# CUBE_SCHEMATIC.net
KiCad netlist of a schematic drawn in Altium Designer
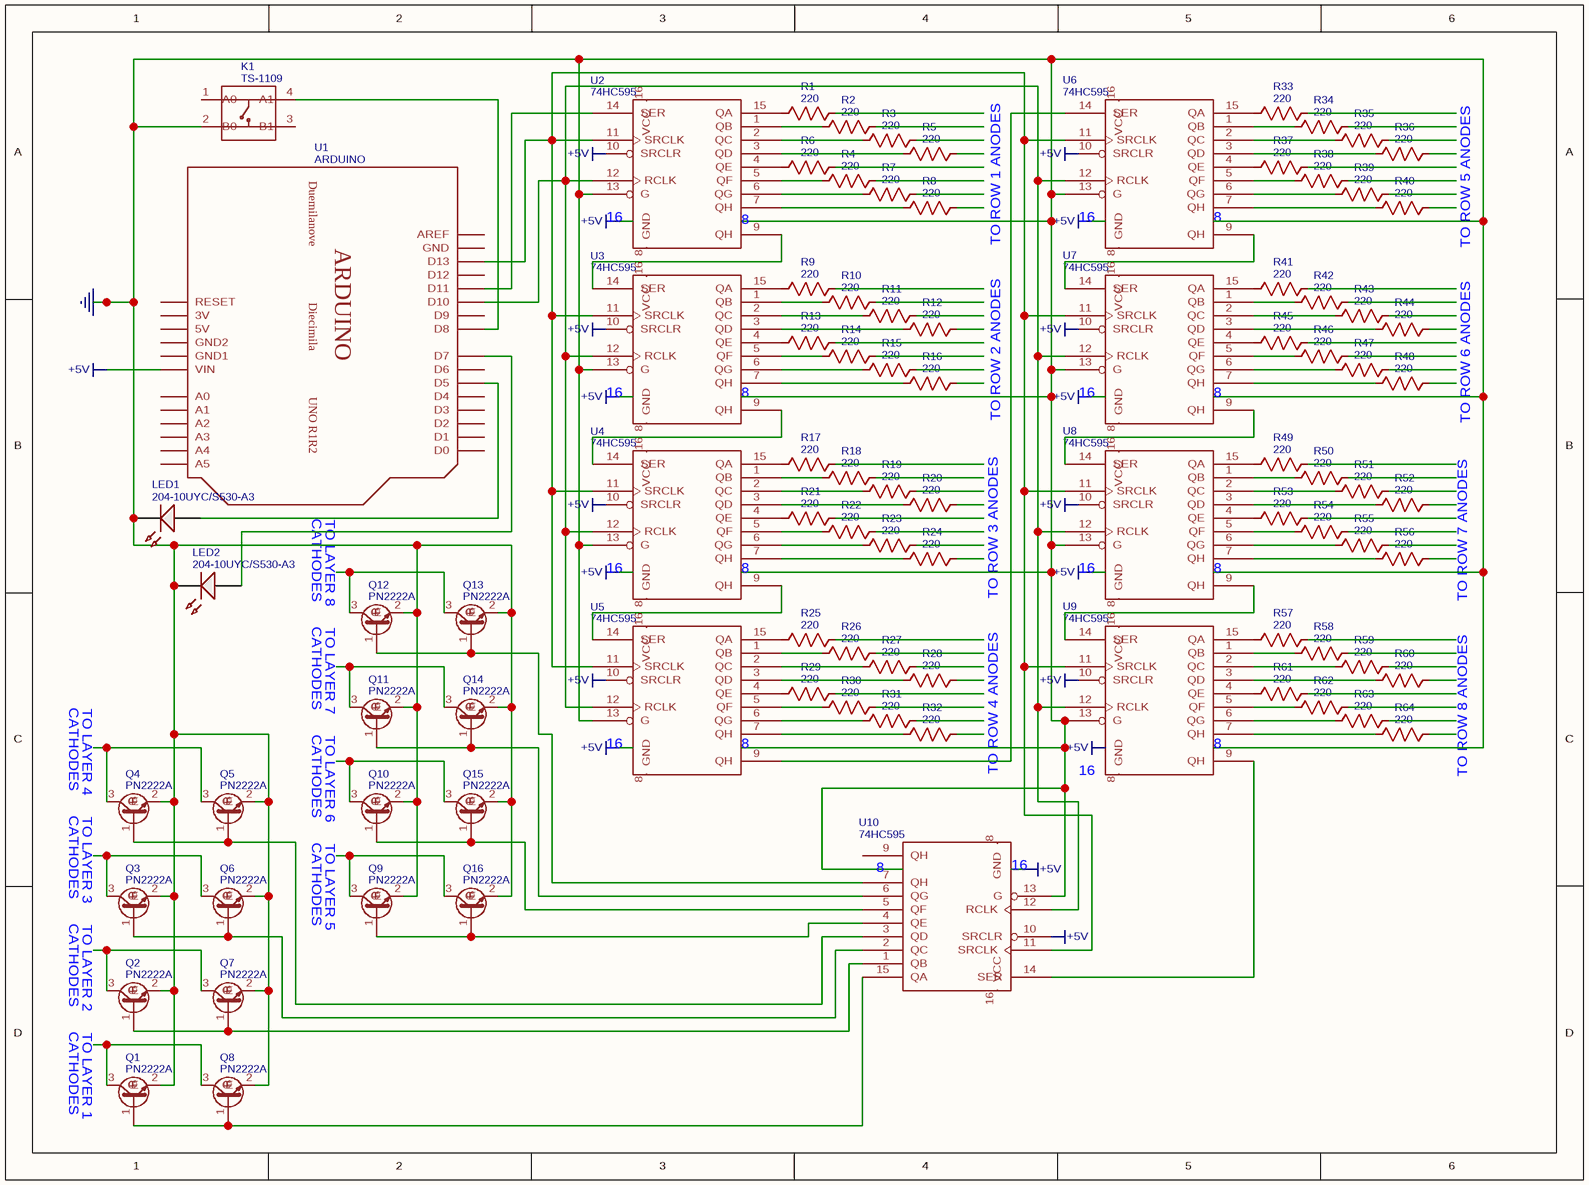
[diagram p0: CUBE+SCHEMATIC.schdoc]

(export (version "E")
  (design (tool "Eeschema 10.0.6"))
  (components
    (comp (ref "K1")
      (value "TS-1109")
      (description "SWITCH TACTILE SPST-NO 0.05A 12V")
      (libsource (lib "") (part "root_0___1"))
    )
    (comp (ref "LED1") (value "204-10UYC/S530-A3") (libsource (lib "") (part "root_2___1")))
    (comp (ref "LED2") (value "204-10UYC/S530-A3") (libsource (lib "") (part "root_2___1")))
    (comp (ref "Q1")
      (value "PN2222A")
      (fields (field (name "BOM_MANUFACTURER PART") "?") (field (name "CONTRIBUTOR") "KiCad"))
      (libsource (lib "altium-import") (part "root_1__"))
    )
    (comp (ref "Q2")
      (value "PN2222A")
      (fields (field (name "BOM_MANUFACTURER PART") "?") (field (name "CONTRIBUTOR") "KiCad"))
      (libsource (lib "altium-import") (part "root_1__"))
    )
    (comp (ref "Q3")
      (value "PN2222A")
      (fields (field (name "BOM_MANUFACTURER PART") "?") (field (name "CONTRIBUTOR") "KiCad"))
      (libsource (lib "altium-import") (part "root_1__"))
    )
    (comp (ref "Q4")
      (value "PN2222A")
      (fields (field (name "BOM_MANUFACTURER PART") "?") (field (name "CONTRIBUTOR") "KiCad"))
      (libsource (lib "altium-import") (part "root_1__"))
    )
    (comp (ref "Q5")
      (value "PN2222A")
      (fields (field (name "BOM_MANUFACTURER PART") "?") (field (name "CONTRIBUTOR") "KiCad"))
      (libsource (lib "altium-import") (part "root_1__"))
    )
    (comp (ref "Q6")
      (value "PN2222A")
      (fields (field (name "BOM_MANUFACTURER PART") "?") (field (name "CONTRIBUTOR") "KiCad"))
      (libsource (lib "altium-import") (part "root_1__"))
    )
    (comp (ref "Q7")
      (value "PN2222A")
      (fields (field (name "BOM_MANUFACTURER PART") "?") (field (name "CONTRIBUTOR") "KiCad"))
      (libsource (lib "altium-import") (part "root_1__"))
    )
    (comp (ref "Q8")
      (value "PN2222A")
      (fields (field (name "BOM_MANUFACTURER PART") "?") (field (name "CONTRIBUTOR") "KiCad"))
      (libsource (lib "altium-import") (part "root_1__"))
    )
    (comp (ref "Q9")
      (value "PN2222A")
      (fields (field (name "BOM_MANUFACTURER PART") "?") (field (name "CONTRIBUTOR") "KiCad"))
      (libsource (lib "altium-import") (part "root_1__"))
    )
    (comp (ref "Q10")
      (value "PN2222A")
      (fields (field (name "BOM_MANUFACTURER PART") "?") (field (name "CONTRIBUTOR") "KiCad"))
      (libsource (lib "altium-import") (part "root_1__"))
    )
    (comp (ref "Q11")
      (value "PN2222A")
      (fields (field (name "BOM_MANUFACTURER PART") "?") (field (name "CONTRIBUTOR") "KiCad"))
      (libsource (lib "altium-import") (part "root_1__"))
    )
    (comp (ref "Q12")
      (value "PN2222A")
      (fields (field (name "BOM_MANUFACTURER PART") "?") (field (name "CONTRIBUTOR") "KiCad"))
      (libsource (lib "altium-import") (part "root_1__"))
    )
    (comp (ref "Q13")
      (value "PN2222A")
      (fields (field (name "BOM_MANUFACTURER PART") "?") (field (name "CONTRIBUTOR") "KiCad"))
      (libsource (lib "altium-import") (part "root_1__"))
    )
    (comp (ref "Q14")
      (value "PN2222A")
      (fields (field (name "BOM_MANUFACTURER PART") "?") (field (name "CONTRIBUTOR") "KiCad"))
      (libsource (lib "altium-import") (part "root_1__"))
    )
    (comp (ref "Q15")
      (value "PN2222A")
      (fields (field (name "BOM_MANUFACTURER PART") "?") (field (name "CONTRIBUTOR") "KiCad"))
      (libsource (lib "altium-import") (part "root_1__"))
    )
    (comp (ref "Q16")
      (value "PN2222A")
      (fields (field (name "BOM_MANUFACTURER PART") "?") (field (name "CONTRIBUTOR") "KiCad"))
      (libsource (lib "altium-import") (part "root_1__"))
    )
    (comp (ref "R1")
      (value "220")
      (fields (field (name "BOM_MANUFACTURER PART") "?"))
      (libsource (lib "altium-import") (part "root_2__"))
    )
    (comp (ref "R2")
      (value "220")
      (fields (field (name "BOM_MANUFACTURER PART") "?"))
      (libsource (lib "altium-import") (part "root_2__"))
    )
    (comp (ref "R3")
      (value "220")
      (fields (field (name "BOM_MANUFACTURER PART") "?"))
      (libsource (lib "altium-import") (part "root_2__"))
    )
    (comp (ref "R4")
      (value "220")
      (fields (field (name "BOM_MANUFACTURER PART") "?"))
      (libsource (lib "altium-import") (part "root_2__"))
    )
    (comp (ref "R5")
      (value "220")
      (fields (field (name "BOM_MANUFACTURER PART") "?"))
      (libsource (lib "altium-import") (part "root_2__"))
    )
    (comp (ref "R6")
      (value "220")
      (fields (field (name "BOM_MANUFACTURER PART") "?"))
      (libsource (lib "altium-import") (part "root_2__"))
    )
    (comp (ref "R7")
      (value "220")
      (fields (field (name "BOM_MANUFACTURER PART") "?"))
      (libsource (lib "altium-import") (part "root_2__"))
    )
    (comp (ref "R8")
      (value "220")
      (fields (field (name "BOM_MANUFACTURER PART") "?"))
      (libsource (lib "altium-import") (part "root_2__"))
    )
    (comp (ref "R9")
      (value "220")
      (fields (field (name "BOM_MANUFACTURER PART") "?"))
      (libsource (lib "altium-import") (part "root_2__"))
    )
    (comp (ref "R10")
      (value "220")
      (fields (field (name "BOM_MANUFACTURER PART") "?"))
      (libsource (lib "altium-import") (part "root_2__"))
    )
    (comp (ref "R11")
      (value "220")
      (fields (field (name "BOM_MANUFACTURER PART") "?"))
      (libsource (lib "altium-import") (part "root_2__"))
    )
    (comp (ref "R12")
      (value "220")
      (fields (field (name "BOM_MANUFACTURER PART") "?"))
      (libsource (lib "altium-import") (part "root_2__"))
    )
    (comp (ref "R13")
      (value "220")
      (fields (field (name "BOM_MANUFACTURER PART") "?"))
      (libsource (lib "altium-import") (part "root_2__"))
    )
    (comp (ref "R14")
      (value "220")
      (fields (field (name "BOM_MANUFACTURER PART") "?"))
      (libsource (lib "altium-import") (part "root_2__"))
    )
    (comp (ref "R15")
      (value "220")
      (fields (field (name "BOM_MANUFACTURER PART") "?"))
      (libsource (lib "altium-import") (part "root_2__"))
    )
    (comp (ref "R16")
      (value "220")
      (fields (field (name "BOM_MANUFACTURER PART") "?"))
      (libsource (lib "altium-import") (part "root_2__"))
    )
    (comp (ref "R17")
      (value "220")
      (fields (field (name "BOM_MANUFACTURER PART") "?"))
      (libsource (lib "altium-import") (part "root_2__"))
    )
    (comp (ref "R18")
      (value "220")
      (fields (field (name "BOM_MANUFACTURER PART") "?"))
      (libsource (lib "altium-import") (part "root_2__"))
    )
    (comp (ref "R19")
      (value "220")
      (fields (field (name "BOM_MANUFACTURER PART") "?"))
      (libsource (lib "altium-import") (part "root_2__"))
    )
    (comp (ref "R20")
      (value "220")
      (fields (field (name "BOM_MANUFACTURER PART") "?"))
      (libsource (lib "altium-import") (part "root_2__"))
    )
    (comp (ref "R21")
      (value "220")
      (fields (field (name "BOM_MANUFACTURER PART") "?"))
      (libsource (lib "altium-import") (part "root_2__"))
    )
    (comp (ref "R22")
      (value "220")
      (fields (field (name "BOM_MANUFACTURER PART") "?"))
      (libsource (lib "altium-import") (part "root_2__"))
    )
    (comp (ref "R23")
      (value "220")
      (fields (field (name "BOM_MANUFACTURER PART") "?"))
      (libsource (lib "altium-import") (part "root_2__"))
    )
    (comp (ref "R24")
      (value "220")
      (fields (field (name "BOM_MANUFACTURER PART") "?"))
      (libsource (lib "altium-import") (part "root_2__"))
    )
    (comp (ref "R25")
      (value "220")
      (fields (field (name "BOM_MANUFACTURER PART") "?"))
      (libsource (lib "altium-import") (part "root_2__"))
    )
    (comp (ref "R26")
      (value "220")
      (fields (field (name "BOM_MANUFACTURER PART") "?"))
      (libsource (lib "altium-import") (part "root_2__"))
    )
    (comp (ref "R27")
      (value "220")
      (fields (field (name "BOM_MANUFACTURER PART") "?"))
      (libsource (lib "altium-import") (part "root_2__"))
    )
    (comp (ref "R28")
      (value "220")
      (fields (field (name "BOM_MANUFACTURER PART") "?"))
      (libsource (lib "altium-import") (part "root_2__"))
    )
    (comp (ref "R29")
      (value "220")
      (fields (field (name "BOM_MANUFACTURER PART") "?"))
      (libsource (lib "altium-import") (part "root_2__"))
    )
    (comp (ref "R30")
      (value "220")
      (fields (field (name "BOM_MANUFACTURER PART") "?"))
      (libsource (lib "altium-import") (part "root_2__"))
    )
    (comp (ref "R31")
      (value "220")
      (fields (field (name "BOM_MANUFACTURER PART") "?"))
      (libsource (lib "altium-import") (part "root_2__"))
    )
    (comp (ref "R32")
      (value "220")
      (fields (field (name "BOM_MANUFACTURER PART") "?"))
      (libsource (lib "altium-import") (part "root_2__"))
    )
    (comp (ref "R33")
      (value "220")
      (fields (field (name "BOM_MANUFACTURER PART") "?"))
      (libsource (lib "altium-import") (part "root_2__"))
    )
    (comp (ref "R34")
      (value "220")
      (fields (field (name "BOM_MANUFACTURER PART") "?"))
      (libsource (lib "altium-import") (part "root_2__"))
    )
    (comp (ref "R35")
      (value "220")
      (fields (field (name "BOM_MANUFACTURER PART") "?"))
      (libsource (lib "altium-import") (part "root_2__"))
    )
    (comp (ref "R36")
      (value "220")
      (fields (field (name "BOM_MANUFACTURER PART") "?"))
      (libsource (lib "altium-import") (part "root_2__"))
    )
    (comp (ref "R37")
      (value "220")
      (fields (field (name "BOM_MANUFACTURER PART") "?"))
      (libsource (lib "altium-import") (part "root_2__"))
    )
    (comp (ref "R38")
      (value "220")
      (fields (field (name "BOM_MANUFACTURER PART") "?"))
      (libsource (lib "altium-import") (part "root_2__"))
    )
    (comp (ref "R39")
      (value "220")
      (fields (field (name "BOM_MANUFACTURER PART") "?"))
      (libsource (lib "altium-import") (part "root_2__"))
    )
    (comp (ref "R40")
      (value "220")
      (fields (field (name "BOM_MANUFACTURER PART") "?"))
      (libsource (lib "altium-import") (part "root_2__"))
    )
    (comp (ref "R41")
      (value "220")
      (fields (field (name "BOM_MANUFACTURER PART") "?"))
      (libsource (lib "altium-import") (part "root_2__"))
    )
    (comp (ref "R42")
      (value "220")
      (fields (field (name "BOM_MANUFACTURER PART") "?"))
      (libsource (lib "altium-import") (part "root_2__"))
    )
    (comp (ref "R43")
      (value "220")
      (fields (field (name "BOM_MANUFACTURER PART") "?"))
      (libsource (lib "altium-import") (part "root_2__"))
    )
    (comp (ref "R44")
      (value "220")
      (fields (field (name "BOM_MANUFACTURER PART") "?"))
      (libsource (lib "altium-import") (part "root_2__"))
    )
    (comp (ref "R45")
      (value "220")
      (fields (field (name "BOM_MANUFACTURER PART") "?"))
      (libsource (lib "altium-import") (part "root_2__"))
    )
    (comp (ref "R46")
      (value "220")
      (fields (field (name "BOM_MANUFACTURER PART") "?"))
      (libsource (lib "altium-import") (part "root_2__"))
    )
    (comp (ref "R47")
      (value "220")
      (fields (field (name "BOM_MANUFACTURER PART") "?"))
      (libsource (lib "altium-import") (part "root_2__"))
    )
    (comp (ref "R48")
      (value "220")
      (fields (field (name "BOM_MANUFACTURER PART") "?"))
      (libsource (lib "altium-import") (part "root_2__"))
    )
    (comp (ref "R49")
      (value "220")
      (fields (field (name "BOM_MANUFACTURER PART") "?"))
      (libsource (lib "altium-import") (part "root_2__"))
    )
    (comp (ref "R50")
      (value "220")
      (fields (field (name "BOM_MANUFACTURER PART") "?"))
      (libsource (lib "altium-import") (part "root_2__"))
    )
    (comp (ref "R51")
      (value "220")
      (fields (field (name "BOM_MANUFACTURER PART") "?"))
      (libsource (lib "altium-import") (part "root_2__"))
    )
    (comp (ref "R52")
      (value "220")
      (fields (field (name "BOM_MANUFACTURER PART") "?"))
      (libsource (lib "altium-import") (part "root_2__"))
    )
    (comp (ref "R53")
      (value "220")
      (fields (field (name "BOM_MANUFACTURER PART") "?"))
      (libsource (lib "altium-import") (part "root_2__"))
    )
    (comp (ref "R54")
      (value "220")
      (fields (field (name "BOM_MANUFACTURER PART") "?"))
      (libsource (lib "altium-import") (part "root_2__"))
    )
    (comp (ref "R55")
      (value "220")
      (fields (field (name "BOM_MANUFACTURER PART") "?"))
      (libsource (lib "altium-import") (part "root_2__"))
    )
    (comp (ref "R56")
      (value "220")
      (fields (field (name "BOM_MANUFACTURER PART") "?"))
      (libsource (lib "altium-import") (part "root_2__"))
    )
    (comp (ref "R57")
      (value "220")
      (fields (field (name "BOM_MANUFACTURER PART") "?"))
      (libsource (lib "altium-import") (part "root_2__"))
    )
    (comp (ref "R58")
      (value "220")
      (fields (field (name "BOM_MANUFACTURER PART") "?"))
      (libsource (lib "altium-import") (part "root_2__"))
    )
    (comp (ref "R59")
      (value "220")
      (fields (field (name "BOM_MANUFACTURER PART") "?"))
      (libsource (lib "altium-import") (part "root_2__"))
    )
    (comp (ref "R60")
      (value "220")
      (fields (field (name "BOM_MANUFACTURER PART") "?"))
      (libsource (lib "altium-import") (part "root_2__"))
    )
    (comp (ref "R61")
      (value "220")
      (fields (field (name "BOM_MANUFACTURER PART") "?"))
      (libsource (lib "altium-import") (part "root_2__"))
    )
    (comp (ref "R62")
      (value "220")
      (fields (field (name "BOM_MANUFACTURER PART") "?"))
      (libsource (lib "altium-import") (part "root_2__"))
    )
    (comp (ref "R63")
      (value "220")
      (fields (field (name "BOM_MANUFACTURER PART") "?"))
      (libsource (lib "altium-import") (part "root_2__"))
    )
    (comp (ref "R64")
      (value "220")
      (fields (field (name "BOM_MANUFACTURER PART") "?"))
      (libsource (lib "altium-import") (part "root_2__"))
    )
    (comp (ref "U1")
      (value "ARDUINO")
      (fields (field (name "BOM_MANUFACTURER PART") "?") (field (name "CONTRIBUTOR") "Adafruit"))
      (libsource (lib "altium-import") (part "root_3__"))
    )
    (comp (ref "U2")
      (value "74HC595")
      (fields (field (name "BOM_MANUFACTURER PART") "?") (field (name "CONTRIBUTOR") "KiCad"))
      (libsource (lib "altium-import") (part "root_0__"))
    )
    (comp (ref "U3")
      (value "74HC595")
      (fields (field (name "BOM_MANUFACTURER PART") "?") (field (name "CONTRIBUTOR") "KiCad"))
      (libsource (lib "altium-import") (part "root_0__"))
    )
    (comp (ref "U4")
      (value "74HC595")
      (fields (field (name "BOM_MANUFACTURER PART") "?") (field (name "CONTRIBUTOR") "KiCad"))
      (libsource (lib "altium-import") (part "root_0__"))
    )
    (comp (ref "U5")
      (value "74HC595")
      (fields (field (name "BOM_MANUFACTURER PART") "?") (field (name "CONTRIBUTOR") "KiCad"))
      (libsource (lib "altium-import") (part "root_0__"))
    )
    (comp (ref "U6")
      (value "74HC595")
      (fields (field (name "BOM_MANUFACTURER PART") "?") (field (name "CONTRIBUTOR") "KiCad"))
      (libsource (lib "altium-import") (part "root_0__"))
    )
    (comp (ref "U7")
      (value "74HC595")
      (fields (field (name "BOM_MANUFACTURER PART") "?") (field (name "CONTRIBUTOR") "KiCad"))
      (libsource (lib "altium-import") (part "root_0__"))
    )
    (comp (ref "U8")
      (value "74HC595")
      (fields (field (name "BOM_MANUFACTURER PART") "?") (field (name "CONTRIBUTOR") "KiCad"))
      (libsource (lib "altium-import") (part "root_0__"))
    )
    (comp (ref "U9")
      (value "74HC595")
      (fields (field (name "BOM_MANUFACTURER PART") "?") (field (name "CONTRIBUTOR") "KiCad"))
      (libsource (lib "altium-import") (part "root_0__"))
    )
    (comp (ref "U10")
      (value "74HC595")
      (fields (field (name "BOM_MANUFACTURER PART") "?") (field (name "CONTRIBUTOR") "KiCad"))
      (libsource (lib "") (part "root_2___2"))
    )
  )
  (nets
    (net (code "1") (name "+5V") (class "Default")
      (node (ref "U1") (pin "VIN") (pinfunction "VIN_VIN") (pintype "passive"))
      (node (ref "U10") (pin "10") (pinfunction "SRCLR_10") (pintype "passive"))
    )
    (net (code "2") (name "GND") (class "Default")
      (node (ref "K1") (pin "2") (pinfunction "B0_2") (pintype "passive"))
      (node (ref "LED1") (pin "2") (pinfunction "C_2") (pintype "passive"))
      (node (ref "LED2") (pin "2") (pinfunction "C_2") (pintype "passive"))
      (node (ref "Q1") (pin "2") (pinfunction "E_2") (pintype "passive"))
      (node (ref "Q10") (pin "2") (pinfunction "E_2") (pintype "passive"))
      (node (ref "Q11") (pin "2") (pinfunction "E_2") (pintype "passive"))
      (node (ref "Q12") (pin "2") (pinfunction "E_2") (pintype "passive"))
      (node (ref "Q13") (pin "2") (pinfunction "E_2") (pintype "passive"))
      (node (ref "Q14") (pin "2") (pinfunction "E_2") (pintype "passive"))
      (node (ref "Q15") (pin "2") (pinfunction "E_2") (pintype "passive"))
      (node (ref "Q16") (pin "2") (pinfunction "E_2") (pintype "passive"))
      (node (ref "Q2") (pin "2") (pinfunction "E_2") (pintype "passive"))
      (node (ref "Q3") (pin "2") (pinfunction "E_2") (pintype "passive"))
      (node (ref "Q4") (pin "2") (pinfunction "E_2") (pintype "passive"))
      (node (ref "Q5") (pin "2") (pinfunction "E_2") (pintype "passive"))
      (node (ref "Q6") (pin "2") (pinfunction "E_2") (pintype "passive"))
      (node (ref "Q7") (pin "2") (pinfunction "E_2") (pintype "passive"))
      (node (ref "Q8") (pin "2") (pinfunction "E_2") (pintype "passive"))
      (node (ref "Q9") (pin "2") (pinfunction "E_2") (pintype "passive"))
      (node (ref "U10") (pin "13") (pinfunction "G_13") (pintype "passive"))
      (node (ref "U2") (pin "13") (pinfunction "G_13") (pintype "passive"))
      (node (ref "U3") (pin "13") (pinfunction "G_13") (pintype "passive"))
      (node (ref "U4") (pin "13") (pinfunction "G_13") (pintype "passive"))
      (node (ref "U5") (pin "13") (pinfunction "G_13") (pintype "passive"))
      (node (ref "U6") (pin "13") (pinfunction "G_13") (pintype "passive"))
      (node (ref "U7") (pin "13") (pinfunction "G_13") (pintype "passive"))
      (node (ref "U8") (pin "13") (pinfunction "G_13") (pintype "passive"))
      (node (ref "U9") (pin "13") (pinfunction "G_13") (pintype "passive"))
    )
    (net (code "3") (name "Net-(K1-A1)") (class "Default")
      (node (ref "K1") (pin "4") (pinfunction "A1_4") (pintype "passive"))
      (node (ref "U1") (pin "D8") (pinfunction "D8_D8") (pintype "passive"))
    )
    (net (code "4") (name "Net-(LED1-A)") (class "Default")
      (node (ref "LED1") (pin "1") (pinfunction "A_1") (pintype "passive"))
      (node (ref "U1") (pin "D5") (pinfunction "D5_D5") (pintype "passive"))
    )
    (net (code "5") (name "Net-(LED2-A)") (class "Default")
      (node (ref "LED2") (pin "1") (pinfunction "A_1") (pintype "passive"))
      (node (ref "U1") (pin "D7") (pinfunction "D7_D7") (pintype "passive"))
    )
    (net (code "6") (name "Net-(Q1-B)") (class "Default")
      (node (ref "Q1") (pin "1") (pinfunction "B_1") (pintype "passive"))
      (node (ref "Q8") (pin "1") (pinfunction "B_1") (pintype "passive"))
      (node (ref "U10") (pin "15") (pinfunction "QA_15") (pintype "passive"))
    )
    (net (code "7") (name "Net-(Q1-C)") (class "Default")
      (node (ref "Q1") (pin "3") (pinfunction "C_3") (pintype "passive"))
      (node (ref "Q8") (pin "3") (pinfunction "C_3") (pintype "passive"))
    )
    (net (code "8") (name "Net-(Q2-B)") (class "Default")
      (node (ref "Q2") (pin "1") (pinfunction "B_1") (pintype "passive"))
      (node (ref "Q7") (pin "1") (pinfunction "B_1") (pintype "passive"))
      (node (ref "U10") (pin "1") (pinfunction "QB_1") (pintype "passive"))
    )
    (net (code "9") (name "Net-(Q2-C)") (class "Default")
      (node (ref "Q2") (pin "3") (pinfunction "C_3") (pintype "passive"))
      (node (ref "Q7") (pin "3") (pinfunction "C_3") (pintype "passive"))
    )
    (net (code "10") (name "Net-(Q3-B)") (class "Default")
      (node (ref "Q3") (pin "1") (pinfunction "B_1") (pintype "passive"))
      (node (ref "Q6") (pin "1") (pinfunction "B_1") (pintype "passive"))
      (node (ref "U10") (pin "2") (pinfunction "QC_2") (pintype "passive"))
    )
    (net (code "11") (name "Net-(Q3-C)") (class "Default")
      (node (ref "Q3") (pin "3") (pinfunction "C_3") (pintype "passive"))
      (node (ref "Q6") (pin "3") (pinfunction "C_3") (pintype "passive"))
    )
    (net (code "12") (name "Net-(Q4-B)") (class "Default")
      (node (ref "Q4") (pin "1") (pinfunction "B_1") (pintype "passive"))
      (node (ref "Q5") (pin "1") (pinfunction "B_1") (pintype "passive"))
      (node (ref "U10") (pin "3") (pinfunction "QD_3") (pintype "passive"))
    )
    (net (code "13") (name "Net-(Q4-C)") (class "Default")
      (node (ref "Q4") (pin "3") (pinfunction "C_3") (pintype "passive"))
      (node (ref "Q5") (pin "3") (pinfunction "C_3") (pintype "passive"))
    )
    (net (code "14") (name "Net-(Q10-B)") (class "Default")
      (node (ref "Q10") (pin "1") (pinfunction "B_1") (pintype "passive"))
      (node (ref "Q15") (pin "1") (pinfunction "B_1") (pintype "passive"))
      (node (ref "U10") (pin "5") (pinfunction "QF_5") (pintype "passive"))
    )
    (net (code "15") (name "Net-(Q10-C)") (class "Default")
      (node (ref "Q10") (pin "3") (pinfunction "C_3") (pintype "passive"))
      (node (ref "Q15") (pin "3") (pinfunction "C_3") (pintype "passive"))
    )
    (net (code "16") (name "Net-(Q11-B)") (class "Default")
      (node (ref "Q11") (pin "1") (pinfunction "B_1") (pintype "passive"))
      (node (ref "Q14") (pin "1") (pinfunction "B_1") (pintype "passive"))
      (node (ref "U10") (pin "6") (pinfunction "QG_6") (pintype "passive"))
    )
    (net (code "17") (name "Net-(Q11-C)") (class "Default")
      (node (ref "Q11") (pin "3") (pinfunction "C_3") (pintype "passive"))
      (node (ref "Q14") (pin "3") (pinfunction "C_3") (pintype "passive"))
    )
    (net (code "18") (name "Net-(Q12-B)") (class "Default")
      (node (ref "Q12") (pin "1") (pinfunction "B_1") (pintype "passive"))
      (node (ref "Q13") (pin "1") (pinfunction "B_1") (pintype "passive"))
      (node (ref "U10") (pin "7") (pinfunction "QH_7") (pintype "passive"))
    )
    (net (code "19") (name "Net-(Q12-C)") (class "Default")
      (node (ref "Q12") (pin "3") (pinfunction "C_3") (pintype "passive"))
      (node (ref "Q13") (pin "3") (pinfunction "C_3") (pintype "passive"))
    )
    (net (code "20") (name "Net-(Q16-B)") (class "Default")
      (node (ref "Q16") (pin "1") (pinfunction "B_1") (pintype "passive"))
      (node (ref "Q9") (pin "1") (pinfunction "B_1") (pintype "passive"))
      (node (ref "U10") (pin "4") (pinfunction "QE_4") (pintype "passive"))
    )
    (net (code "21") (name "Net-(Q16-C)") (class "Default")
      (node (ref "Q16") (pin "3") (pinfunction "C_3") (pintype "passive"))
      (node (ref "Q9") (pin "3") (pinfunction "C_3") (pintype "passive"))
    )
    (net (code "22") (name "Net-(R8-Pad2)") (class "Default")
      (node (ref "R8") (pin "2") (pinfunction "2_2") (pintype "passive"))
      (node (ref "U2") (pin "7") (pinfunction "QH_7") (pintype "passive"))
    )
    (net (code "23") (name "Net-(R16-Pad2)") (class "Default")
      (node (ref "R16") (pin "2") (pinfunction "2_2") (pintype "passive"))
      (node (ref "U3") (pin "7") (pinfunction "QH_7") (pintype "passive"))
    )
    (net (code "24") (name "Net-(R24-Pad2)") (class "Default")
      (node (ref "R24") (pin "2") (pinfunction "2_2") (pintype "passive"))
      (node (ref "U4") (pin "7") (pinfunction "QH_7") (pintype "passive"))
    )
    (net (code "25") (name "Net-(R32-Pad2)") (class "Default")
      (node (ref "R32") (pin "2") (pinfunction "2_2") (pintype "passive"))
      (node (ref "U5") (pin "7") (pinfunction "QH_7") (pintype "passive"))
    )
    (net (code "26") (name "Net-(R40-Pad2)") (class "Default")
      (node (ref "R40") (pin "2") (pinfunction "2_2") (pintype "passive"))
      (node (ref "U6") (pin "7") (pinfunction "QH_7") (pintype "passive"))
    )
    (net (code "27") (name "Net-(R48-Pad2)") (class "Default")
      (node (ref "R48") (pin "2") (pinfunction "2_2") (pintype "passive"))
      (node (ref "U7") (pin "7") (pinfunction "QH_7") (pintype "passive"))
    )
    (net (code "28") (name "Net-(R56-Pad2)") (class "Default")
      (node (ref "R56") (pin "2") (pinfunction "2_2") (pintype "passive"))
      (node (ref "U8") (pin "7") (pinfunction "QH_7") (pintype "passive"))
    )
    (net (code "29") (name "Net-(R64-Pad2)") (class "Default")
      (node (ref "R64") (pin "2") (pinfunction "2_2") (pintype "passive"))
      (node (ref "U9") (pin "7") (pinfunction "QH_7") (pintype "passive"))
    )
    (net (code "30") (name "Net-(U2-QA)") (class "Default")
      (node (ref "R1") (pin "2") (pinfunction "2_2") (pintype "passive"))
      (node (ref "U2") (pin "15") (pinfunction "QA_15") (pintype "passive"))
    )
    (net (code "31") (name "Net-(U2-QB)") (class "Default")
      (node (ref "R2") (pin "2") (pinfunction "2_2") (pintype "passive"))
      (node (ref "U2") (pin "1") (pinfunction "QB_1") (pintype "passive"))
    )
    (net (code "32") (name "Net-(U2-QC)") (class "Default")
      (node (ref "R3") (pin "2") (pinfunction "2_2") (pintype "passive"))
      (node (ref "U2") (pin "2") (pinfunction "QC_2") (pintype "passive"))
    )
    (net (code "33") (name "Net-(U2-QD)") (class "Default")
      (node (ref "R5") (pin "2") (pinfunction "2_2") (pintype "passive"))
      (node (ref "U2") (pin "3") (pinfunction "QD_3") (pintype "passive"))
    )
    (net (code "34") (name "Net-(U2-QE)") (class "Default")
      (node (ref "R6") (pin "2") (pinfunction "2_2") (pintype "passive"))
      (node (ref "U2") (pin "4") (pinfunction "QE_4") (pintype "passive"))
    )
    (net (code "35") (name "Net-(U2-QF)") (class "Default")
      (node (ref "R4") (pin "2") (pinfunction "2_2") (pintype "passive"))
      (node (ref "U2") (pin "5") (pinfunction "QF_5") (pintype "passive"))
    )
    (net (code "36") (name "Net-(U2-QG)") (class "Default")
      (node (ref "R7") (pin "2") (pinfunction "2_2") (pintype "passive"))
      (node (ref "U2") (pin "6") (pinfunction "QG_6") (pintype "passive"))
    )
    (net (code "37") (name "Net-(U2-SER)") (class "Default")
      (node (ref "U1") (pin "D11") (pinfunction "D11_D11") (pintype "passive"))
      (node (ref "U2") (pin "14") (pinfunction "SER_14") (pintype "passive"))
    )
    (net (code "38") (name "Net-(U3-QA)") (class "Default")
      (node (ref "R9") (pin "2") (pinfunction "2_2") (pintype "passive"))
      (node (ref "U3") (pin "15") (pinfunction "QA_15") (pintype "passive"))
    )
    (net (code "39") (name "Net-(U3-QB)") (class "Default")
      (node (ref "R10") (pin "2") (pinfunction "2_2") (pintype "passive"))
      (node (ref "U3") (pin "1") (pinfunction "QB_1") (pintype "passive"))
    )
    (net (code "40") (name "Net-(U3-QC)") (class "Default")
      (node (ref "R11") (pin "2") (pinfunction "2_2") (pintype "passive"))
      (node (ref "U3") (pin "2") (pinfunction "QC_2") (pintype "passive"))
    )
    (net (code "41") (name "Net-(U3-QD)") (class "Default")
      (node (ref "R12") (pin "2") (pinfunction "2_2") (pintype "passive"))
      (node (ref "U3") (pin "3") (pinfunction "QD_3") (pintype "passive"))
    )
    (net (code "42") (name "Net-(U3-QE)") (class "Default")
      (node (ref "R13") (pin "2") (pinfunction "2_2") (pintype "passive"))
      (node (ref "U3") (pin "4") (pinfunction "QE_4") (pintype "passive"))
    )
    (net (code "43") (name "Net-(U3-QF)") (class "Default")
      (node (ref "R14") (pin "2") (pinfunction "2_2") (pintype "passive"))
      (node (ref "U3") (pin "5") (pinfunction "QF_5") (pintype "passive"))
    )
    (net (code "44") (name "Net-(U3-QG)") (class "Default")
      (node (ref "R15") (pin "2") (pinfunction "2_2") (pintype "passive"))
      (node (ref "U3") (pin "6") (pinfunction "QG_6") (pintype "passive"))
    )
    (net (code "45") (name "Net-(U3-SER)") (class "Default")
      (node (ref "U2") (pin "9") (pinfunction "QH_9") (pintype "passive"))
      (node (ref "U3") (pin "14") (pinfunction "SER_14") (pintype "passive"))
    )
    (net (code "46") (name "Net-(U4-QA)") (class "Default")
      (node (ref "R17") (pin "2") (pinfunction "2_2") (pintype "passive"))
      (node (ref "U4") (pin "15") (pinfunction "QA_15") (pintype "passive"))
    )
    (net (code "47") (name "Net-(U4-QB)") (class "Default")
      (node (ref "R18") (pin "2") (pinfunction "2_2") (pintype "passive"))
      (node (ref "U4") (pin "1") (pinfunction "QB_1") (pintype "passive"))
    )
    (net (code "48") (name "Net-(U4-QC)") (class "Default")
      (node (ref "R19") (pin "2") (pinfunction "2_2") (pintype "passive"))
      (node (ref "U4") (pin "2") (pinfunction "QC_2") (pintype "passive"))
    )
    (net (code "49") (name "Net-(U4-QD)") (class "Default")
      (node (ref "R20") (pin "2") (pinfunction "2_2") (pintype "passive"))
      (node (ref "U4") (pin "3") (pinfunction "QD_3") (pintype "passive"))
    )
    (net (code "50") (name "Net-(U4-QE)") (class "Default")
      (node (ref "R21") (pin "2") (pinfunction "2_2") (pintype "passive"))
      (node (ref "U4") (pin "4") (pinfunction "QE_4") (pintype "passive"))
    )
    (net (code "51") (name "Net-(U4-QF)") (class "Default")
      (node (ref "R22") (pin "2") (pinfunction "2_2") (pintype "passive"))
      (node (ref "U4") (pin "5") (pinfunction "QF_5") (pintype "passive"))
    )
    (net (code "52") (name "Net-(U4-QG)") (class "Default")
      (node (ref "R23") (pin "2") (pinfunction "2_2") (pintype "passive"))
      (node (ref "U4") (pin "6") (pinfunction "QG_6") (pintype "passive"))
    )
    (net (code "53") (name "Net-(U4-SER)") (class "Default")
      (node (ref "U3") (pin "9") (pinfunction "QH_9") (pintype "passive"))
      (node (ref "U4") (pin "14") (pinfunction "SER_14") (pintype "passive"))
    )
    (net (code "54") (name "Net-(U5-QA)") (class "Default")
      (node (ref "R25") (pin "2") (pinfunction "2_2") (pintype "passive"))
      (node (ref "U5") (pin "15") (pinfunction "QA_15") (pintype "passive"))
    )
    (net (code "55") (name "Net-(U5-QB)") (class "Default")
      (node (ref "R26") (pin "2") (pinfunction "2_2") (pintype "passive"))
      (node (ref "U5") (pin "1") (pinfunction "QB_1") (pintype "passive"))
    )
    (net (code "56") (name "Net-(U5-QC)") (class "Default")
      (node (ref "R27") (pin "2") (pinfunction "2_2") (pintype "passive"))
      (node (ref "U5") (pin "2") (pinfunction "QC_2") (pintype "passive"))
    )
    (net (code "57") (name "Net-(U5-QD)") (class "Default")
      (node (ref "R28") (pin "2") (pinfunction "2_2") (pintype "passive"))
      (node (ref "U5") (pin "3") (pinfunction "QD_3") (pintype "passive"))
    )
    (net (code "58") (name "Net-(U5-QE)") (class "Default")
      (node (ref "R29") (pin "2") (pinfunction "2_2") (pintype "passive"))
      (node (ref "U5") (pin "4") (pinfunction "QE_4") (pintype "passive"))
    )
    (net (code "59") (name "Net-(U5-QF)") (class "Default")
      (node (ref "R30") (pin "2") (pinfunction "2_2") (pintype "passive"))
      (node (ref "U5") (pin "5") (pinfunction "QF_5") (pintype "passive"))
    )
    (net (code "60") (name "Net-(U5-QG)") (class "Default")
      (node (ref "R31") (pin "2") (pinfunction "2_2") (pintype "passive"))
      (node (ref "U5") (pin "6") (pinfunction "QG_6") (pintype "passive"))
    )
    (net (code "61") (name "Net-(U5-SER)") (class "Default")
      (node (ref "U4") (pin "9") (pinfunction "QH_9") (pintype "passive"))
      (node (ref "U5") (pin "14") (pinfunction "SER_14") (pintype "passive"))
    )
    (net (code "62") (name "Net-(U6-QA)") (class "Default")
      (node (ref "R33") (pin "2") (pinfunction "2_2") (pintype "passive"))
      (node (ref "U6") (pin "15") (pinfunction "QA_15") (pintype "passive"))
    )
    (net (code "63") (name "Net-(U6-QB)") (class "Default")
      (node (ref "R34") (pin "2") (pinfunction "2_2") (pintype "passive"))
      (node (ref "U6") (pin "1") (pinfunction "QB_1") (pintype "passive"))
    )
    (net (code "64") (name "Net-(U6-QC)") (class "Default")
      (node (ref "R35") (pin "2") (pinfunction "2_2") (pintype "passive"))
      (node (ref "U6") (pin "2") (pinfunction "QC_2") (pintype "passive"))
    )
    (net (code "65") (name "Net-(U6-QD)") (class "Default")
      (node (ref "R36") (pin "2") (pinfunction "2_2") (pintype "passive"))
      (node (ref "U6") (pin "3") (pinfunction "QD_3") (pintype "passive"))
    )
    (net (code "66") (name "Net-(U6-QE)") (class "Default")
      (node (ref "R37") (pin "2") (pinfunction "2_2") (pintype "passive"))
      (node (ref "U6") (pin "4") (pinfunction "QE_4") (pintype "passive"))
    )
    (net (code "67") (name "Net-(U6-QF)") (class "Default")
      (node (ref "R38") (pin "2") (pinfunction "2_2") (pintype "passive"))
      (node (ref "U6") (pin "5") (pinfunction "QF_5") (pintype "passive"))
    )
    (net (code "68") (name "Net-(U6-QG)") (class "Default")
      (node (ref "R39") (pin "2") (pinfunction "2_2") (pintype "passive"))
      (node (ref "U6") (pin "6") (pinfunction "QG_6") (pintype "passive"))
    )
    (net (code "69") (name "Net-(U6-SER)") (class "Default")
      (node (ref "U5") (pin "9") (pinfunction "QH_9") (pintype "passive"))
      (node (ref "U6") (pin "14") (pinfunction "SER_14") (pintype "passive"))
    )
    (net (code "70") (name "Net-(U7-QA)") (class "Default")
      (node (ref "R41") (pin "2") (pinfunction "2_2") (pintype "passive"))
      (node (ref "U7") (pin "15") (pinfunction "QA_15") (pintype "passive"))
    )
    (net (code "71") (name "Net-(U7-QB)") (class "Default")
      (node (ref "R42") (pin "2") (pinfunction "2_2") (pintype "passive"))
      (node (ref "U7") (pin "1") (pinfunction "QB_1") (pintype "passive"))
    )
    (net (code "72") (name "Net-(U7-QC)") (class "Default")
      (node (ref "R43") (pin "2") (pinfunction "2_2") (pintype "passive"))
      (node (ref "U7") (pin "2") (pinfunction "QC_2") (pintype "passive"))
    )
    (net (code "73") (name "Net-(U7-QD)") (class "Default")
      (node (ref "R44") (pin "2") (pinfunction "2_2") (pintype "passive"))
      (node (ref "U7") (pin "3") (pinfunction "QD_3") (pintype "passive"))
    )
    (net (code "74") (name "Net-(U7-QE)") (class "Default")
      (node (ref "R45") (pin "2") (pinfunction "2_2") (pintype "passive"))
      (node (ref "U7") (pin "4") (pinfunction "QE_4") (pintype "passive"))
    )
    (net (code "75") (name "Net-(U7-QF)") (class "Default")
      (node (ref "R46") (pin "2") (pinfunction "2_2") (pintype "passive"))
      (node (ref "U7") (pin "5") (pinfunction "QF_5") (pintype "passive"))
    )
    (net (code "76") (name "Net-(U7-QG)") (class "Default")
      (node (ref "R47") (pin "2") (pinfunction "2_2") (pintype "passive"))
      (node (ref "U7") (pin "6") (pinfunction "QG_6") (pintype "passive"))
    )
    (net (code "77") (name "Net-(U7-SER)") (class "Default")
      (node (ref "U6") (pin "9") (pinfunction "QH_9") (pintype "passive"))
      (node (ref "U7") (pin "14") (pinfunction "SER_14") (pintype "passive"))
    )
    (net (code "78") (name "Net-(U8-QA)") (class "Default")
      (node (ref "R49") (pin "2") (pinfunction "2_2") (pintype "passive"))
      (node (ref "U8") (pin "15") (pinfunction "QA_15") (pintype "passive"))
    )
    (net (code "79") (name "Net-(U8-QB)") (class "Default")
      (node (ref "R50") (pin "2") (pinfunction "2_2") (pintype "passive"))
      (node (ref "U8") (pin "1") (pinfunction "QB_1") (pintype "passive"))
    )
    (net (code "80") (name "Net-(U8-QC)") (class "Default")
      (node (ref "R51") (pin "2") (pinfunction "2_2") (pintype "passive"))
      (node (ref "U8") (pin "2") (pinfunction "QC_2") (pintype "passive"))
    )
    (net (code "81") (name "Net-(U8-QD)") (class "Default")
      (node (ref "R52") (pin "2") (pinfunction "2_2") (pintype "passive"))
      (node (ref "U8") (pin "3") (pinfunction "QD_3") (pintype "passive"))
    )
    (net (code "82") (name "Net-(U8-QE)") (class "Default")
      (node (ref "R53") (pin "2") (pinfunction "2_2") (pintype "passive"))
      (node (ref "U8") (pin "4") (pinfunction "QE_4") (pintype "passive"))
    )
    (net (code "83") (name "Net-(U8-QF)") (class "Default")
      (node (ref "R54") (pin "2") (pinfunction "2_2") (pintype "passive"))
      (node (ref "U8") (pin "5") (pinfunction "QF_5") (pintype "passive"))
    )
    (net (code "84") (name "Net-(U8-QG)") (class "Default")
      (node (ref "R55") (pin "2") (pinfunction "2_2") (pintype "passive"))
      (node (ref "U8") (pin "6") (pinfunction "QG_6") (pintype "passive"))
    )
    (net (code "85") (name "Net-(U8-SER)") (class "Default")
      (node (ref "U7") (pin "9") (pinfunction "QH_9") (pintype "passive"))
      (node (ref "U8") (pin "14") (pinfunction "SER_14") (pintype "passive"))
    )
    (net (code "86") (name "Net-(U9-QA)") (class "Default")
      (node (ref "R57") (pin "2") (pinfunction "2_2") (pintype "passive"))
      (node (ref "U9") (pin "15") (pinfunction "QA_15") (pintype "passive"))
    )
    (net (code "87") (name "Net-(U9-QB)") (class "Default")
      (node (ref "R58") (pin "2") (pinfunction "2_2") (pintype "passive"))
      (node (ref "U9") (pin "1") (pinfunction "QB_1") (pintype "passive"))
    )
    (net (code "88") (name "Net-(U9-QC)") (class "Default")
      (node (ref "R59") (pin "2") (pinfunction "2_2") (pintype "passive"))
      (node (ref "U9") (pin "2") (pinfunction "QC_2") (pintype "passive"))
    )
    (net (code "89") (name "Net-(U9-QD)") (class "Default")
      (node (ref "R60") (pin "2") (pinfunction "2_2") (pintype "passive"))
      (node (ref "U9") (pin "3") (pinfunction "QD_3") (pintype "passive"))
    )
    (net (code "90") (name "Net-(U9-QE)") (class "Default")
      (node (ref "R61") (pin "2") (pinfunction "2_2") (pintype "passive"))
      (node (ref "U9") (pin "4") (pinfunction "QE_4") (pintype "passive"))
    )
    (net (code "91") (name "Net-(U9-QF)") (class "Default")
      (node (ref "R62") (pin "2") (pinfunction "2_2") (pintype "passive"))
      (node (ref "U9") (pin "5") (pinfunction "QF_5") (pintype "passive"))
    )
    (net (code "92") (name "Net-(U9-QG)") (class "Default")
      (node (ref "R63") (pin "2") (pinfunction "2_2") (pintype "passive"))
      (node (ref "U9") (pin "6") (pinfunction "QG_6") (pintype "passive"))
    )
    (net (code "93") (name "Net-(U9-SER)") (class "Default")
      (node (ref "U8") (pin "9") (pinfunction "QH_9") (pintype "passive"))
      (node (ref "U9") (pin "14") (pinfunction "SER_14") (pintype "passive"))
    )
    (net (code "94") (name "Net-(U10-RCLK)") (class "Default")
      (node (ref "U1") (pin "D10") (pinfunction "D10_D10") (pintype "passive"))
      (node (ref "U10") (pin "12") (pinfunction "RCLK_12") (pintype "passive"))
      (node (ref "U2") (pin "12") (pinfunction "RCLK_12") (pintype "passive"))
      (node (ref "U3") (pin "12") (pinfunction "RCLK_12") (pintype "passive"))
      (node (ref "U4") (pin "12") (pinfunction "RCLK_12") (pintype "passive"))
      (node (ref "U5") (pin "12") (pinfunction "RCLK_12") (pintype "passive"))
      (node (ref "U6") (pin "12") (pinfunction "RCLK_12") (pintype "passive"))
      (node (ref "U7") (pin "12") (pinfunction "RCLK_12") (pintype "passive"))
      (node (ref "U8") (pin "12") (pinfunction "RCLK_12") (pintype "passive"))
      (node (ref "U9") (pin "12") (pinfunction "RCLK_12") (pintype "passive"))
    )
    (net (code "95") (name "Net-(U10-SER)") (class "Default")
      (node (ref "U10") (pin "14") (pinfunction "SER_14") (pintype "passive"))
      (node (ref "U9") (pin "9") (pinfunction "QH_9") (pintype "passive"))
    )
    (net (code "96") (name "Net-(U10-SRCLK)") (class "Default")
      (node (ref "U1") (pin "D13") (pinfunction "D13_D13") (pintype "passive"))
      (node (ref "U10") (pin "11") (pinfunction "SRCLK_11") (pintype "passive"))
      (node (ref "U2") (pin "11") (pinfunction "SRCLK_11") (pintype "passive"))
      (node (ref "U3") (pin "11") (pinfunction "SRCLK_11") (pintype "passive"))
      (node (ref "U4") (pin "11") (pinfunction "SRCLK_11") (pintype "passive"))
      (node (ref "U5") (pin "11") (pinfunction "SRCLK_11") (pintype "passive"))
      (node (ref "U6") (pin "11") (pinfunction "SRCLK_11") (pintype "passive"))
      (node (ref "U7") (pin "11") (pinfunction "SRCLK_11") (pintype "passive"))
      (node (ref "U8") (pin "11") (pinfunction "SRCLK_11") (pintype "passive"))
      (node (ref "U9") (pin "11") (pinfunction "SRCLK_11") (pintype "passive"))
    )
    (net (code "97") (name "unconnected-(K1-A0-Pad1)") (class "Default")
      (node (ref "K1") (pin "1") (pinfunction "A0_1") (pintype "passive"))
    )
    (net (code "98") (name "unconnected-(K1-B1-Pad3)") (class "Default")
      (node (ref "K1") (pin "3") (pinfunction "B1_3") (pintype "passive"))
    )
    (net (code "99") (name "unconnected-(R1-Pad1)") (class "Default")
      (node (ref "R1") (pin "1") (pinfunction "1_1") (pintype "passive"))
    )
    (net (code "100") (name "unconnected-(R2-Pad1)") (class "Default")
      (node (ref "R2") (pin "1") (pinfunction "1_1") (pintype "passive"))
    )
    (net (code "101") (name "unconnected-(R3-Pad1)") (class "Default")
      (node (ref "R3") (pin "1") (pinfunction "1_1") (pintype "passive"))
    )
    (net (code "102") (name "unconnected-(R4-Pad1)") (class "Default")
      (node (ref "R4") (pin "1") (pinfunction "1_1") (pintype "passive"))
    )
    (net (code "103") (name "unconnected-(R5-Pad1)") (class "Default")
      (node (ref "R5") (pin "1") (pinfunction "1_1") (pintype "passive"))
    )
    (net (code "104") (name "unconnected-(R6-Pad1)") (class "Default")
      (node (ref "R6") (pin "1") (pinfunction "1_1") (pintype "passive"))
    )
    (net (code "105") (name "unconnected-(R7-Pad1)") (class "Default")
      (node (ref "R7") (pin "1") (pinfunction "1_1") (pintype "passive"))
    )
    (net (code "106") (name "unconnected-(R8-Pad1)") (class "Default")
      (node (ref "R8") (pin "1") (pinfunction "1_1") (pintype "passive"))
    )
    (net (code "107") (name "unconnected-(R9-Pad1)") (class "Default")
      (node (ref "R9") (pin "1") (pinfunction "1_1") (pintype "passive"))
    )
    (net (code "108") (name "unconnected-(R10-Pad1)") (class "Default")
      (node (ref "R10") (pin "1") (pinfunction "1_1") (pintype "passive"))
    )
    (net (code "109") (name "unconnected-(R11-Pad1)") (class "Default")
      (node (ref "R11") (pin "1") (pinfunction "1_1") (pintype "passive"))
    )
    (net (code "110") (name "unconnected-(R12-Pad1)") (class "Default")
      (node (ref "R12") (pin "1") (pinfunction "1_1") (pintype "passive"))
    )
    (net (code "111") (name "unconnected-(R13-Pad1)") (class "Default")
      (node (ref "R13") (pin "1") (pinfunction "1_1") (pintype "passive"))
    )
    (net (code "112") (name "unconnected-(R14-Pad1)") (class "Default")
      (node (ref "R14") (pin "1") (pinfunction "1_1") (pintype "passive"))
    )
    (net (code "113") (name "unconnected-(R15-Pad1)") (class "Default")
      (node (ref "R15") (pin "1") (pinfunction "1_1") (pintype "passive"))
    )
    (net (code "114") (name "unconnected-(R16-Pad1)") (class "Default")
      (node (ref "R16") (pin "1") (pinfunction "1_1") (pintype "passive"))
    )
    (net (code "115") (name "unconnected-(R17-Pad1)") (class "Default")
      (node (ref "R17") (pin "1") (pinfunction "1_1") (pintype "passive"))
    )
    (net (code "116") (name "unconnected-(R18-Pad1)") (class "Default")
      (node (ref "R18") (pin "1") (pinfunction "1_1") (pintype "passive"))
    )
    (net (code "117") (name "unconnected-(R19-Pad1)") (class "Default")
      (node (ref "R19") (pin "1") (pinfunction "1_1") (pintype "passive"))
    )
    (net (code "118") (name "unconnected-(R20-Pad1)") (class "Default")
      (node (ref "R20") (pin "1") (pinfunction "1_1") (pintype "passive"))
    )
    (net (code "119") (name "unconnected-(R21-Pad1)") (class "Default")
      (node (ref "R21") (pin "1") (pinfunction "1_1") (pintype "passive"))
    )
    (net (code "120") (name "unconnected-(R22-Pad1)") (class "Default")
      (node (ref "R22") (pin "1") (pinfunction "1_1") (pintype "passive"))
    )
    (net (code "121") (name "unconnected-(R23-Pad1)") (class "Default")
      (node (ref "R23") (pin "1") (pinfunction "1_1") (pintype "passive"))
    )
    (net (code "122") (name "unconnected-(R24-Pad1)") (class "Default")
      (node (ref "R24") (pin "1") (pinfunction "1_1") (pintype "passive"))
    )
    (net (code "123") (name "unconnected-(R25-Pad1)") (class "Default")
      (node (ref "R25") (pin "1") (pinfunction "1_1") (pintype "passive"))
    )
    (net (code "124") (name "unconnected-(R26-Pad1)") (class "Default")
      (node (ref "R26") (pin "1") (pinfunction "1_1") (pintype "passive"))
    )
    (net (code "125") (name "unconnected-(R27-Pad1)") (class "Default")
      (node (ref "R27") (pin "1") (pinfunction "1_1") (pintype "passive"))
    )
    (net (code "126") (name "unconnected-(R28-Pad1)") (class "Default")
      (node (ref "R28") (pin "1") (pinfunction "1_1") (pintype "passive"))
    )
    (net (code "127") (name "unconnected-(R29-Pad1)") (class "Default")
      (node (ref "R29") (pin "1") (pinfunction "1_1") (pintype "passive"))
    )
    (net (code "128") (name "unconnected-(R30-Pad1)") (class "Default")
      (node (ref "R30") (pin "1") (pinfunction "1_1") (pintype "passive"))
    )
    (net (code "129") (name "unconnected-(R31-Pad1)") (class "Default")
      (node (ref "R31") (pin "1") (pinfunction "1_1") (pintype "passive"))
    )
    (net (code "130") (name "unconnected-(R32-Pad1)") (class "Default")
      (node (ref "R32") (pin "1") (pinfunction "1_1") (pintype "passive"))
    )
    (net (code "131") (name "unconnected-(R33-Pad1)") (class "Default")
      (node (ref "R33") (pin "1") (pinfunction "1_1") (pintype "passive"))
    )
    (net (code "132") (name "unconnected-(R34-Pad1)") (class "Default")
      (node (ref "R34") (pin "1") (pinfunction "1_1") (pintype "passive"))
    )
    (net (code "133") (name "unconnected-(R35-Pad1)") (class "Default")
      (node (ref "R35") (pin "1") (pinfunction "1_1") (pintype "passive"))
    )
    (net (code "134") (name "unconnected-(R36-Pad1)") (class "Default")
      (node (ref "R36") (pin "1") (pinfunction "1_1") (pintype "passive"))
    )
    (net (code "135") (name "unconnected-(R37-Pad1)") (class "Default")
      (node (ref "R37") (pin "1") (pinfunction "1_1") (pintype "passive"))
    )
    (net (code "136") (name "unconnected-(R38-Pad1)") (class "Default")
      (node (ref "R38") (pin "1") (pinfunction "1_1") (pintype "passive"))
    )
    (net (code "137") (name "unconnected-(R39-Pad1)") (class "Default")
      (node (ref "R39") (pin "1") (pinfunction "1_1") (pintype "passive"))
    )
    (net (code "138") (name "unconnected-(R40-Pad1)") (class "Default")
      (node (ref "R40") (pin "1") (pinfunction "1_1") (pintype "passive"))
    )
    (net (code "139") (name "unconnected-(R41-Pad1)") (class "Default")
      (node (ref "R41") (pin "1") (pinfunction "1_1") (pintype "passive"))
    )
    (net (code "140") (name "unconnected-(R42-Pad1)") (class "Default")
      (node (ref "R42") (pin "1") (pinfunction "1_1") (pintype "passive"))
    )
    (net (code "141") (name "unconnected-(R43-Pad1)") (class "Default")
      (node (ref "R43") (pin "1") (pinfunction "1_1") (pintype "passive"))
    )
    (net (code "142") (name "unconnected-(R44-Pad1)") (class "Default")
      (node (ref "R44") (pin "1") (pinfunction "1_1") (pintype "passive"))
    )
    (net (code "143") (name "unconnected-(R45-Pad1)") (class "Default")
      (node (ref "R45") (pin "1") (pinfunction "1_1") (pintype "passive"))
    )
    (net (code "144") (name "unconnected-(R46-Pad1)") (class "Default")
      (node (ref "R46") (pin "1") (pinfunction "1_1") (pintype "passive"))
    )
    (net (code "145") (name "unconnected-(R47-Pad1)") (class "Default")
      (node (ref "R47") (pin "1") (pinfunction "1_1") (pintype "passive"))
    )
    (net (code "146") (name "unconnected-(R48-Pad1)") (class "Default")
      (node (ref "R48") (pin "1") (pinfunction "1_1") (pintype "passive"))
    )
    (net (code "147") (name "unconnected-(R49-Pad1)") (class "Default")
      (node (ref "R49") (pin "1") (pinfunction "1_1") (pintype "passive"))
    )
    (net (code "148") (name "unconnected-(R50-Pad1)") (class "Default")
      (node (ref "R50") (pin "1") (pinfunction "1_1") (pintype "passive"))
    )
    (net (code "149") (name "unconnected-(R51-Pad1)") (class "Default")
      (node (ref "R51") (pin "1") (pinfunction "1_1") (pintype "passive"))
    )
    (net (code "150") (name "unconnected-(R52-Pad1)") (class "Default")
      (node (ref "R52") (pin "1") (pinfunction "1_1") (pintype "passive"))
    )
    (net (code "151") (name "unconnected-(R53-Pad1)") (class "Default")
      (node (ref "R53") (pin "1") (pinfunction "1_1") (pintype "passive"))
    )
    (net (code "152") (name "unconnected-(R54-Pad1)") (class "Default")
      (node (ref "R54") (pin "1") (pinfunction "1_1") (pintype "passive"))
    )
    (net (code "153") (name "unconnected-(R55-Pad1)") (class "Default")
      (node (ref "R55") (pin "1") (pinfunction "1_1") (pintype "passive"))
    )
    (net (code "154") (name "unconnected-(R56-Pad1)") (class "Default")
      (node (ref "R56") (pin "1") (pinfunction "1_1") (pintype "passive"))
    )
    (net (code "155") (name "unconnected-(R57-Pad1)") (class "Default")
      (node (ref "R57") (pin "1") (pinfunction "1_1") (pintype "passive"))
    )
    (net (code "156") (name "unconnected-(R58-Pad1)") (class "Default")
      (node (ref "R58") (pin "1") (pinfunction "1_1") (pintype "passive"))
    )
    (net (code "157") (name "unconnected-(R59-Pad1)") (class "Default")
      (node (ref "R59") (pin "1") (pinfunction "1_1") (pintype "passive"))
    )
    (net (code "158") (name "unconnected-(R60-Pad1)") (class "Default")
      (node (ref "R60") (pin "1") (pinfunction "1_1") (pintype "passive"))
    )
    (net (code "159") (name "unconnected-(R61-Pad1)") (class "Default")
      (node (ref "R61") (pin "1") (pinfunction "1_1") (pintype "passive"))
    )
    (net (code "160") (name "unconnected-(R62-Pad1)") (class "Default")
      (node (ref "R62") (pin "1") (pinfunction "1_1") (pintype "passive"))
    )
    (net (code "161") (name "unconnected-(R63-Pad1)") (class "Default")
      (node (ref "R63") (pin "1") (pinfunction "1_1") (pintype "passive"))
    )
    (net (code "162") (name "unconnected-(R64-Pad1)") (class "Default")
      (node (ref "R64") (pin "1") (pinfunction "1_1") (pintype "passive"))
    )
    (net (code "163") (name "unconnected-(U1-Pad3V)") (class "Default")
      (node (ref "U1") (pin "3V") (pinfunction "3V_3V") (pintype "passive"))
    )
    (net (code "164") (name "unconnected-(U1-Pad5V)") (class "Default")
      (node (ref "U1") (pin "5V") (pinfunction "5V_5V") (pintype "passive"))
    )
    (net (code "165") (name "unconnected-(U1-PadA0)") (class "Default")
      (node (ref "U1") (pin "A0") (pinfunction "A0_A0") (pintype "passive"))
    )
    (net (code "166") (name "unconnected-(U1-PadA1)") (class "Default")
      (node (ref "U1") (pin "A1") (pinfunction "A1_A1") (pintype "passive"))
    )
    (net (code "167") (name "unconnected-(U1-PadA2)") (class "Default")
      (node (ref "U1") (pin "A2") (pinfunction "A2_A2") (pintype "passive"))
    )
    (net (code "168") (name "unconnected-(U1-PadA3)") (class "Default")
      (node (ref "U1") (pin "A3") (pinfunction "A3_A3") (pintype "passive"))
    )
    (net (code "169") (name "unconnected-(U1-PadA4)") (class "Default")
      (node (ref "U1") (pin "A4") (pinfunction "A4_A4") (pintype "passive"))
    )
    (net (code "170") (name "unconnected-(U1-PadA5)") (class "Default")
      (node (ref "U1") (pin "A5") (pinfunction "A5_A5") (pintype "passive"))
    )
    (net (code "171") (name "unconnected-(U1-PadAREF)") (class "Default")
      (node (ref "U1") (pin "AREF") (pinfunction "AREF_AREF") (pintype "passive"))
    )
    (net (code "172") (name "unconnected-(U1-PadD0)") (class "Default")
      (node (ref "U1") (pin "D0") (pinfunction "D0_D0") (pintype "passive"))
    )
    (net (code "173") (name "unconnected-(U1-PadD1)") (class "Default")
      (node (ref "U1") (pin "D1") (pinfunction "D1_D1") (pintype "passive"))
    )
    (net (code "174") (name "unconnected-(U1-PadD2)") (class "Default")
      (node (ref "U1") (pin "D2") (pinfunction "D2_D2") (pintype "passive"))
    )
    (net (code "175") (name "unconnected-(U1-PadD3)") (class "Default")
      (node (ref "U1") (pin "D3") (pinfunction "D3_D3") (pintype "passive"))
    )
    (net (code "176") (name "unconnected-(U1-PadD4)") (class "Default")
      (node (ref "U1") (pin "D4") (pinfunction "D4_D4") (pintype "passive"))
    )
    (net (code "177") (name "unconnected-(U1-PadD6)") (class "Default")
      (node (ref "U1") (pin "D6") (pinfunction "D6_D6") (pintype "passive"))
    )
    (net (code "178") (name "unconnected-(U1-PadD9)") (class "Default")
      (node (ref "U1") (pin "D9") (pinfunction "D9_D9") (pintype "passive"))
    )
    (net (code "179") (name "unconnected-(U1-PadD12)") (class "Default")
      (node (ref "U1") (pin "D12") (pinfunction "D12_D12") (pintype "passive"))
    )
    (net (code "180") (name "unconnected-(U1-PadGND)") (class "Default")
      (node (ref "U1") (pin "GND") (pinfunction "GND_GND") (pintype "passive"))
    )
    (net (code "181") (name "unconnected-(U1-PadGND1)") (class "Default")
      (node (ref "U1") (pin "GND1") (pinfunction "GND1_GND1") (pintype "passive"))
    )
    (net (code "182") (name "unconnected-(U1-PadGND2)") (class "Default")
      (node (ref "U1") (pin "GND2") (pinfunction "GND2_GND2") (pintype "passive"))
    )
    (net (code "183") (name "unconnected-(U1-PadRESET)") (class "Default")
      (node (ref "U1") (pin "RESET") (pinfunction "RESET_RESET") (pintype "passive"))
    )
    (net (code "184") (name "unconnected-(U2-GND-Pad8)") (class "Default")
      (node (ref "U2") (pin "8") (pinfunction "GND_8") (pintype "passive"))
    )
    (net (code "185") (name "unconnected-(U2-SRCLR-Pad10)") (class "Default")
      (node (ref "U2") (pin "10") (pinfunction "SRCLR_10") (pintype "passive"))
    )
    (net (code "186") (name "unconnected-(U2-VCC-Pad16)") (class "Default")
      (node (ref "U2") (pin "16") (pinfunction "VCC_16") (pintype "passive"))
    )
    (net (code "187") (name "unconnected-(U3-GND-Pad8)") (class "Default")
      (node (ref "U3") (pin "8") (pinfunction "GND_8") (pintype "passive"))
    )
    (net (code "188") (name "unconnected-(U3-SRCLR-Pad10)") (class "Default")
      (node (ref "U3") (pin "10") (pinfunction "SRCLR_10") (pintype "passive"))
    )
    (net (code "189") (name "unconnected-(U3-VCC-Pad16)") (class "Default")
      (node (ref "U3") (pin "16") (pinfunction "VCC_16") (pintype "passive"))
    )
    (net (code "190") (name "unconnected-(U4-GND-Pad8)") (class "Default")
      (node (ref "U4") (pin "8") (pinfunction "GND_8") (pintype "passive"))
    )
    (net (code "191") (name "unconnected-(U4-SRCLR-Pad10)") (class "Default")
      (node (ref "U4") (pin "10") (pinfunction "SRCLR_10") (pintype "passive"))
    )
    (net (code "192") (name "unconnected-(U4-VCC-Pad16)") (class "Default")
      (node (ref "U4") (pin "16") (pinfunction "VCC_16") (pintype "passive"))
    )
    (net (code "193") (name "unconnected-(U5-GND-Pad8)") (class "Default")
      (node (ref "U5") (pin "8") (pinfunction "GND_8") (pintype "passive"))
    )
    (net (code "194") (name "unconnected-(U5-SRCLR-Pad10)") (class "Default")
      (node (ref "U5") (pin "10") (pinfunction "SRCLR_10") (pintype "passive"))
    )
    (net (code "195") (name "unconnected-(U5-VCC-Pad16)") (class "Default")
      (node (ref "U5") (pin "16") (pinfunction "VCC_16") (pintype "passive"))
    )
    (net (code "196") (name "unconnected-(U6-GND-Pad8)") (class "Default")
      (node (ref "U6") (pin "8") (pinfunction "GND_8") (pintype "passive"))
    )
    (net (code "197") (name "unconnected-(U6-SRCLR-Pad10)") (class "Default")
      (node (ref "U6") (pin "10") (pinfunction "SRCLR_10") (pintype "passive"))
    )
    (net (code "198") (name "unconnected-(U6-VCC-Pad16)") (class "Default")
      (node (ref "U6") (pin "16") (pinfunction "VCC_16") (pintype "passive"))
    )
    (net (code "199") (name "unconnected-(U7-GND-Pad8)") (class "Default")
      (node (ref "U7") (pin "8") (pinfunction "GND_8") (pintype "passive"))
    )
    (net (code "200") (name "unconnected-(U7-SRCLR-Pad10)") (class "Default")
      (node (ref "U7") (pin "10") (pinfunction "SRCLR_10") (pintype "passive"))
    )
    (net (code "201") (name "unconnected-(U7-VCC-Pad16)") (class "Default")
      (node (ref "U7") (pin "16") (pinfunction "VCC_16") (pintype "passive"))
    )
    (net (code "202") (name "unconnected-(U8-GND-Pad8)") (class "Default")
      (node (ref "U8") (pin "8") (pinfunction "GND_8") (pintype "passive"))
    )
    (net (code "203") (name "unconnected-(U8-SRCLR-Pad10)") (class "Default")
      (node (ref "U8") (pin "10") (pinfunction "SRCLR_10") (pintype "passive"))
    )
    (net (code "204") (name "unconnected-(U8-VCC-Pad16)") (class "Default")
      (node (ref "U8") (pin "16") (pinfunction "VCC_16") (pintype "passive"))
    )
    (net (code "205") (name "unconnected-(U9-GND-Pad8)") (class "Default")
      (node (ref "U9") (pin "8") (pinfunction "GND_8") (pintype "passive"))
    )
    (net (code "206") (name "unconnected-(U9-SRCLR-Pad10)") (class "Default")
      (node (ref "U9") (pin "10") (pinfunction "SRCLR_10") (pintype "passive"))
    )
    (net (code "207") (name "unconnected-(U9-VCC-Pad16)") (class "Default")
      (node (ref "U9") (pin "16") (pinfunction "VCC_16") (pintype "passive"))
    )
    (net (code "208") (name "unconnected-(U10-GND-Pad8)") (class "Default")
      (node (ref "U10") (pin "8") (pinfunction "GND_8") (pintype "passive"))
    )
    (net (code "209") (name "unconnected-(U10-QH-Pad9)") (class "Default")
      (node (ref "U10") (pin "9") (pinfunction "QH_9") (pintype "passive"))
    )
    (net (code "210") (name "unconnected-(U10-VCC-Pad16)") (class "Default")
      (node (ref "U10") (pin "16") (pinfunction "VCC_16") (pintype "passive"))
    )
  )
)
